# Lightbox_schematic_29OCT.net
KiCad netlist of a schematic drawn in EAGLE
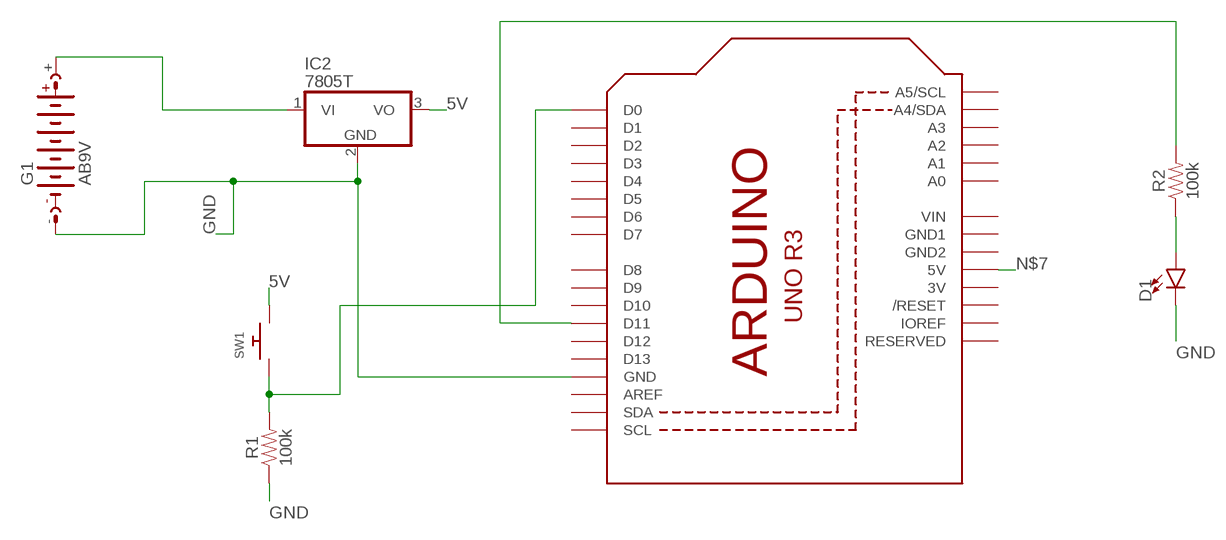
[diagram p0: schematic, sheet 1]

(export (version "E")
  (design (tool "Eeschema 10.0.6"))
  (components
    (comp (ref "D1")
      (value "LED3MM")
      (footprint "eagle-import:LED_3MM")
      (libsource (lib "eagle-import") (part "LED3MM"))
    )
    (comp (ref "G1")
      (value "AB9V")
      (footprint "eagle-import:AB9V")
      (libsource (lib "eagle-import") (part "AB9V"))
    )
    (comp (ref "IC2")
      (value "7805T")
      (footprint "eagle-import:TO220H")
      (libsource (lib "eagle-import") (part "78T05"))
    )
    (comp (ref "R1")
      (value "100k")
      (footprint "eagle-import:AXIAL-0.3")
      (libsource (lib "eagle-import") (part "100KOHM-HORIZ-1/4W-1%"))
    )
    (comp (ref "R2")
      (value "100k")
      (footprint "eagle-import:AXIAL-0.3")
      (libsource (lib "eagle-import") (part "100KOHM-HORIZ-1/4W-1%"))
    )
    (comp (ref "SW1")
      (value "SWITCH_PUSHBUTTONSOFTTOUCHSMD_SJ")
      (footprint "eagle-import:PUSHBUTTON_SMD_SJ")
      (libsource (lib "eagle-import") (part "SWITCH_PUSHBUTTONSOFTTOUCHSMD_SJ"))
    )
    (comp (ref "U1")
      (value "ARDUINOR3-DIMENSION")
      (footprint "eagle-import:ARDUINOR3")
      (libsource (lib "eagle-import") (part "ARDUINOR3-DIMENSION"))
    )
  )
  (nets
    (net (code "1") (name "/3V") (class "Default")
      (node (ref "U1") (pin "3V") (pinfunction "3V_3V") (pintype "power_in"))
    )
    (net (code "2") (name "/5V") (class "Default")
      (node (ref "IC2") (pin "3") (pinfunction "VO_3") (pintype "passive"))
      (node (ref "SW1") (pin "P$2") (pinfunction "P$2_P$2") (pintype "passive"))
    )
    (net (code "3") (name "/GND") (class "Default")
      (node (ref "D1") (pin "K") (pinfunction "C_K") (pintype "passive"))
      (node (ref "G1") (pin "-") (pinfunction "-_-") (pintype "passive"))
      (node (ref "IC2") (pin "2") (pinfunction "GND_2") (pintype "passive"))
      (node (ref "R1") (pin "P$1") (pinfunction "1_P$1") (pintype "passive"))
      (node (ref "U1") (pin "GND") (pinfunction "GND_GND") (pintype "power_in"))
    )
    (net (code "4") (name "/GND1") (class "Default")
      (node (ref "U1") (pin "GND1") (pinfunction "GND1_GND1") (pintype "power_in"))
    )
    (net (code "5") (name "/GND2") (class "Default")
      (node (ref "U1") (pin "GND2") (pinfunction "GND2_GND2") (pintype "power_in"))
    )
    (net (code "6") (name "/N$7") (class "Default")
      (node (ref "U1") (pin "5V") (pinfunction "5V_5V") (pintype "power_in"))
    )
    (net (code "7") (name "/VIN") (class "Default")
      (node (ref "U1") (pin "VIN") (pinfunction "VIN_VIN") (pintype "power_in"))
    )
    (net (code "8") (name "Net-(IC2-VI)") (class "Default")
      (node (ref "G1") (pin "+") (pinfunction "+_+") (pintype "passive"))
      (node (ref "IC2") (pin "1") (pinfunction "VI_1") (pintype "input"))
    )
    (net (code "9") (name "Net-(R1-2)") (class "Default")
      (node (ref "R1") (pin "P$2") (pinfunction "2_P$2") (pintype "passive"))
      (node (ref "SW1") (pin "P$1") (pinfunction "P$1_P$1") (pintype "passive"))
      (node (ref "U1") (pin "D0") (pinfunction "D0_D0") (pintype "bidirectional"))
    )
    (net (code "10") (name "Net-(R2-1)") (class "Default")
      (node (ref "D1") (pin "A") (pinfunction "A_A") (pintype "passive"))
      (node (ref "R2") (pin "P$1") (pinfunction "1_P$1") (pintype "passive"))
    )
    (net (code "11") (name "Net-(R2-2)") (class "Default")
      (node (ref "R2") (pin "P$2") (pinfunction "2_P$2") (pintype "passive"))
      (node (ref "U1") (pin "D11") (pinfunction "D11_D11") (pintype "bidirectional"))
    )
    (net (code "12") (name "unconnected-(U1-A4{slash}SDA-PadA4)") (class "Default")
      (node (ref "U1") (pin "A4") (pinfunction "A4/SDA_A4") (pintype "bidirectional"))
    )
    (net (code "13") (name "unconnected-(U1-A5{slash}SCL-PadA5)") (class "Default")
      (node (ref "U1") (pin "A5") (pinfunction "A5/SCL_A5") (pintype "bidirectional"))
    )
    (net (code "14") (name "unconnected-(U1-PadA0)") (class "Default")
      (node (ref "U1") (pin "A0") (pinfunction "A0_A0") (pintype "bidirectional"))
    )
    (net (code "15") (name "unconnected-(U1-PadA1)") (class "Default")
      (node (ref "U1") (pin "A1") (pinfunction "A1_A1") (pintype "bidirectional"))
    )
    (net (code "16") (name "unconnected-(U1-PadA2)") (class "Default")
      (node (ref "U1") (pin "A2") (pinfunction "A2_A2") (pintype "bidirectional"))
    )
    (net (code "17") (name "unconnected-(U1-PadA3)") (class "Default")
      (node (ref "U1") (pin "A3") (pinfunction "A3_A3") (pintype "bidirectional"))
    )
    (net (code "18") (name "unconnected-(U1-PadAREF)") (class "Default")
      (node (ref "U1") (pin "AREF") (pinfunction "AREF_AREF") (pintype "bidirectional"))
    )
    (net (code "19") (name "unconnected-(U1-PadD1)") (class "Default")
      (node (ref "U1") (pin "D1") (pinfunction "D1_D1") (pintype "bidirectional"))
    )
    (net (code "20") (name "unconnected-(U1-PadD2)") (class "Default")
      (node (ref "U1") (pin "D2") (pinfunction "D2_D2") (pintype "bidirectional"))
    )
    (net (code "21") (name "unconnected-(U1-PadD3)") (class "Default")
      (node (ref "U1") (pin "D3") (pinfunction "D3_D3") (pintype "bidirectional"))
    )
    (net (code "22") (name "unconnected-(U1-PadD4)") (class "Default")
      (node (ref "U1") (pin "D4") (pinfunction "D4_D4") (pintype "bidirectional"))
    )
    (net (code "23") (name "unconnected-(U1-PadD5)") (class "Default")
      (node (ref "U1") (pin "D5") (pinfunction "D5_D5") (pintype "bidirectional"))
    )
    (net (code "24") (name "unconnected-(U1-PadD6)") (class "Default")
      (node (ref "U1") (pin "D6") (pinfunction "D6_D6") (pintype "bidirectional"))
    )
    (net (code "25") (name "unconnected-(U1-PadD7)") (class "Default")
      (node (ref "U1") (pin "D7") (pinfunction "D7_D7") (pintype "bidirectional"))
    )
    (net (code "26") (name "unconnected-(U1-PadD8)") (class "Default")
      (node (ref "U1") (pin "D8") (pinfunction "D8_D8") (pintype "bidirectional"))
    )
    (net (code "27") (name "unconnected-(U1-PadD9)") (class "Default")
      (node (ref "U1") (pin "D9") (pinfunction "D9_D9") (pintype "bidirectional"))
    )
    (net (code "28") (name "unconnected-(U1-PadD10)") (class "Default")
      (node (ref "U1") (pin "D10") (pinfunction "D10_D10") (pintype "bidirectional"))
    )
    (net (code "29") (name "unconnected-(U1-PadD12)") (class "Default")
      (node (ref "U1") (pin "D12") (pinfunction "D12_D12") (pintype "bidirectional"))
    )
    (net (code "30") (name "unconnected-(U1-PadD13)") (class "Default")
      (node (ref "U1") (pin "D13") (pinfunction "D13_D13") (pintype "bidirectional"))
    )
    (net (code "31") (name "unconnected-(U1-PadIOREF)") (class "Default")
      (node (ref "U1") (pin "IOREF") (pinfunction "IOREF_IOREF") (pintype "output"))
    )
    (net (code "32") (name "unconnected-(U1-PadRESERVED)") (class "Default")
      (node (ref "U1") (pin "RESERVED") (pinfunction "RESERVED_RESERVED") (pintype "no_connect"))
    )
    (net (code "33") (name "unconnected-(U1-PadSCL)") (class "Default")
      (node (ref "U1") (pin "SCL") (pinfunction "SCL_SCL") (pintype "bidirectional"))
    )
    (net (code "34") (name "unconnected-(U1-PadSDA)") (class "Default")
      (node (ref "U1") (pin "SDA") (pinfunction "SDA_SDA") (pintype "bidirectional"))
    )
    (net (code "35") (name "unconnected-(U1-{slash}RESET-PadRESET)") (class "Default")
      (node (ref "U1") (pin "RESET") (pinfunction "/RESET_RESET") (pintype "bidirectional"))
    )
  )
)
